# Piano_Circuit_desgin_Schematic.net
KiCad netlist of a schematic drawn in EAGLE
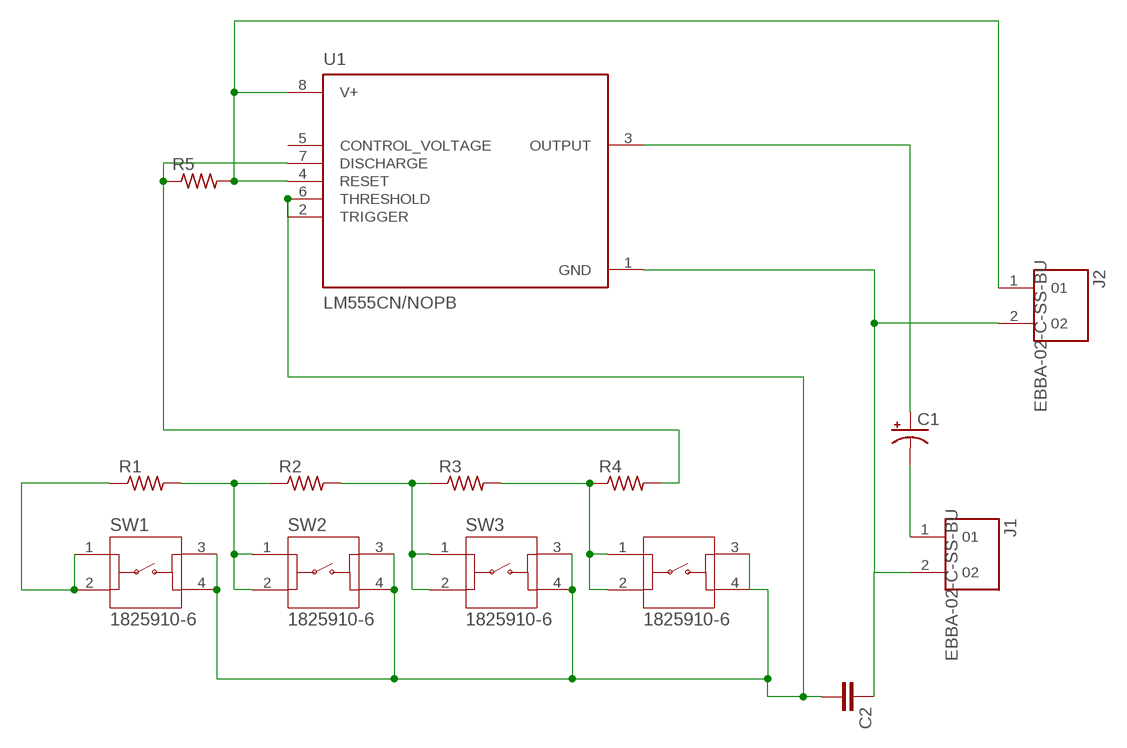
[diagram p0: schematic, sheet 1]

(export (version "E")
  (design (tool "Eeschema 10.0.6"))
  (components
    (comp (ref "C1")
      (value "CPOL-USE2-4")
      (footprint "eagle-import:E2-4")
      (libsource (lib "eagle-import") (part "CPOL-USE2-4"))
    )
    (comp (ref "C2")
      (value "C-EU025-025X050")
      (footprint "eagle-import:C025-025X050")
      (libsource (lib "eagle-import") (part "C-EU025-025X050"))
    )
    (comp (ref "J1")
      (value "EBBA-02-C-SS-BU")
      (footprint "eagle-import:EBBA-02-C-SS-BU")
      (fields (field (name "MF") "Adam Tech"))
      (libsource (lib "eagle-import") (part "EBBA-02-C-SS-BU"))
    )
    (comp (ref "J2")
      (value "EBBA-02-C-SS-BU")
      (footprint "eagle-import:EBBA-02-C-SS-BU")
      (fields (field (name "MF") "Adam Tech"))
      (libsource (lib "eagle-import") (part "EBBA-02-C-SS-BU"))
    )
    (comp (ref "R1")
      (value "R-US_0204/7")
      (footprint "eagle-import:0204_7")
      (libsource (lib "eagle-import") (part "R-US_0204/7"))
    )
    (comp (ref "R2")
      (value "R-US_0204/7")
      (footprint "eagle-import:0204_7")
      (libsource (lib "eagle-import") (part "R-US_0204/7"))
    )
    (comp (ref "R3")
      (value "R-US_0204/7")
      (footprint "eagle-import:0204_7")
      (libsource (lib "eagle-import") (part "R-US_0204/7"))
    )
    (comp (ref "R4")
      (value "R-US_0204/7")
      (footprint "eagle-import:0204_7")
      (libsource (lib "eagle-import") (part "R-US_0204/7"))
    )
    (comp (ref "R5")
      (value "R-US_0204/7")
      (footprint "eagle-import:0204_7")
      (libsource (lib "eagle-import") (part "R-US_0204/7"))
    )
    (comp (ref "SW1")
      (value "1825910-6")
      (footprint "eagle-import:SW_1825910-6-4")
      (fields (field (name "MF") "TE Connectivity"))
      (libsource (lib "eagle-import") (part "1825910-6"))
    )
    (comp (ref "SW2")
      (value "1825910-6")
      (footprint "eagle-import:SW_1825910-6-4")
      (fields (field (name "MF") "TE Connectivity"))
      (libsource (lib "eagle-import") (part "1825910-6"))
    )
    (comp (ref "SW3")
      (value "1825910-6")
      (footprint "eagle-import:SW_1825910-6-4")
      (fields (field (name "MF") "TE Connectivity"))
      (libsource (lib "eagle-import") (part "1825910-6"))
    )
    (comp (ref "SW4")
      (value "1825910-6")
      (footprint "eagle-import:SW_1825910-6-4")
      (fields (field (name "MF") "TE Connectivity"))
      (libsource (lib "eagle-import") (part "1825910-6"))
    )
    (comp (ref "U1")
      (value "LM555CN/NOPB")
      (footprint "eagle-import:DIP794W45P254L959H508Q8")
      (fields (field (name "MF") "Texas Instruments"))
      (libsource (lib "eagle-import") (part "LM555CN/NOPB"))
    )
  )
  (nets
    (net (code "1") (name "Net-(J1-01)") (class "Default")
      (node (ref "C1") (pin "-") (pinfunction "-_-") (pintype "passive"))
      (node (ref "J1") (pin "1") (pinfunction "01_1") (pintype "bidirectional"))
    )
    (net (code "2") (name "Net-(J1-02)") (class "Default")
      (node (ref "C2") (pin "1") (pinfunction "1_1") (pintype "passive"))
      (node (ref "J1") (pin "2") (pinfunction "02_2") (pintype "bidirectional"))
      (node (ref "J2") (pin "2") (pinfunction "02_2") (pintype "bidirectional"))
      (node (ref "U1") (pin "1") (pinfunction "GND_1") (pintype "power_in"))
    )
    (net (code "3") (name "Net-(J2-01)") (class "Default")
      (node (ref "J2") (pin "1") (pinfunction "01_1") (pintype "bidirectional"))
      (node (ref "R5") (pin "2") (pinfunction "2_2") (pintype "passive"))
      (node (ref "U1") (pin "4") (pinfunction "RESET_4") (pintype "input"))
      (node (ref "U1") (pin "8") (pinfunction "V+_8") (pintype "power_in"))
    )
    (net (code "4") (name "Net-(R1-Pad1)") (class "Default")
      (node (ref "R1") (pin "1") (pinfunction "1_1") (pintype "passive"))
      (node (ref "SW1") (pin "1") (pinfunction "1_1") (pintype "passive"))
      (node (ref "SW1") (pin "2") (pinfunction "2_2") (pintype "passive"))
    )
    (net (code "5") (name "Net-(R1-Pad2)") (class "Default")
      (node (ref "R1") (pin "2") (pinfunction "2_2") (pintype "passive"))
      (node (ref "R2") (pin "1") (pinfunction "1_1") (pintype "passive"))
      (node (ref "SW2") (pin "1") (pinfunction "1_1") (pintype "passive"))
      (node (ref "SW2") (pin "2") (pinfunction "2_2") (pintype "passive"))
    )
    (net (code "6") (name "Net-(R2-Pad2)") (class "Default")
      (node (ref "R2") (pin "2") (pinfunction "2_2") (pintype "passive"))
      (node (ref "R3") (pin "1") (pinfunction "1_1") (pintype "passive"))
      (node (ref "SW3") (pin "1") (pinfunction "1_1") (pintype "passive"))
      (node (ref "SW3") (pin "2") (pinfunction "2_2") (pintype "passive"))
    )
    (net (code "7") (name "Net-(R3-Pad2)") (class "Default")
      (node (ref "R3") (pin "2") (pinfunction "2_2") (pintype "passive"))
      (node (ref "R4") (pin "1") (pinfunction "1_1") (pintype "passive"))
      (node (ref "SW4") (pin "1") (pinfunction "1_1") (pintype "passive"))
      (node (ref "SW4") (pin "2") (pinfunction "2_2") (pintype "passive"))
    )
    (net (code "8") (name "Net-(U1-DISCHARGE)") (class "Default")
      (node (ref "R4") (pin "2") (pinfunction "2_2") (pintype "passive"))
      (node (ref "R5") (pin "1") (pinfunction "1_1") (pintype "passive"))
      (node (ref "U1") (pin "7") (pinfunction "DISCHARGE_7") (pintype "input"))
    )
    (net (code "9") (name "Net-(U1-OUTPUT)") (class "Default")
      (node (ref "C1") (pin "+") (pinfunction "+_+") (pintype "passive"))
      (node (ref "U1") (pin "3") (pinfunction "OUTPUT_3") (pintype "output"))
    )
    (net (code "10") (name "Net-(U1-THRESHOLD)") (class "Default")
      (node (ref "C2") (pin "2") (pinfunction "2_2") (pintype "passive"))
      (node (ref "SW1") (pin "3") (pinfunction "3_3") (pintype "passive"))
      (node (ref "SW1") (pin "4") (pinfunction "4_4") (pintype "passive"))
      (node (ref "SW2") (pin "3") (pinfunction "3_3") (pintype "passive"))
      (node (ref "SW2") (pin "4") (pinfunction "4_4") (pintype "passive"))
      (node (ref "SW3") (pin "3") (pinfunction "3_3") (pintype "passive"))
      (node (ref "SW3") (pin "4") (pinfunction "4_4") (pintype "passive"))
      (node (ref "SW4") (pin "3") (pinfunction "3_3") (pintype "passive"))
      (node (ref "SW4") (pin "4") (pinfunction "4_4") (pintype "passive"))
      (node (ref "U1") (pin "2") (pinfunction "TRIGGER_2") (pintype "input"))
      (node (ref "U1") (pin "6") (pinfunction "THRESHOLD_6") (pintype "input"))
    )
    (net (code "11") (name "unconnected-(U1-CONTROL_VOLTAGE-Pad5)") (class "Default")
      (node (ref "U1") (pin "5") (pinfunction "CONTROL_VOLTAGE_5") (pintype "input"))
    )
  )
)
